# PSFB_power.net
KiCad netlist of a schematic drawn in Altium Designer
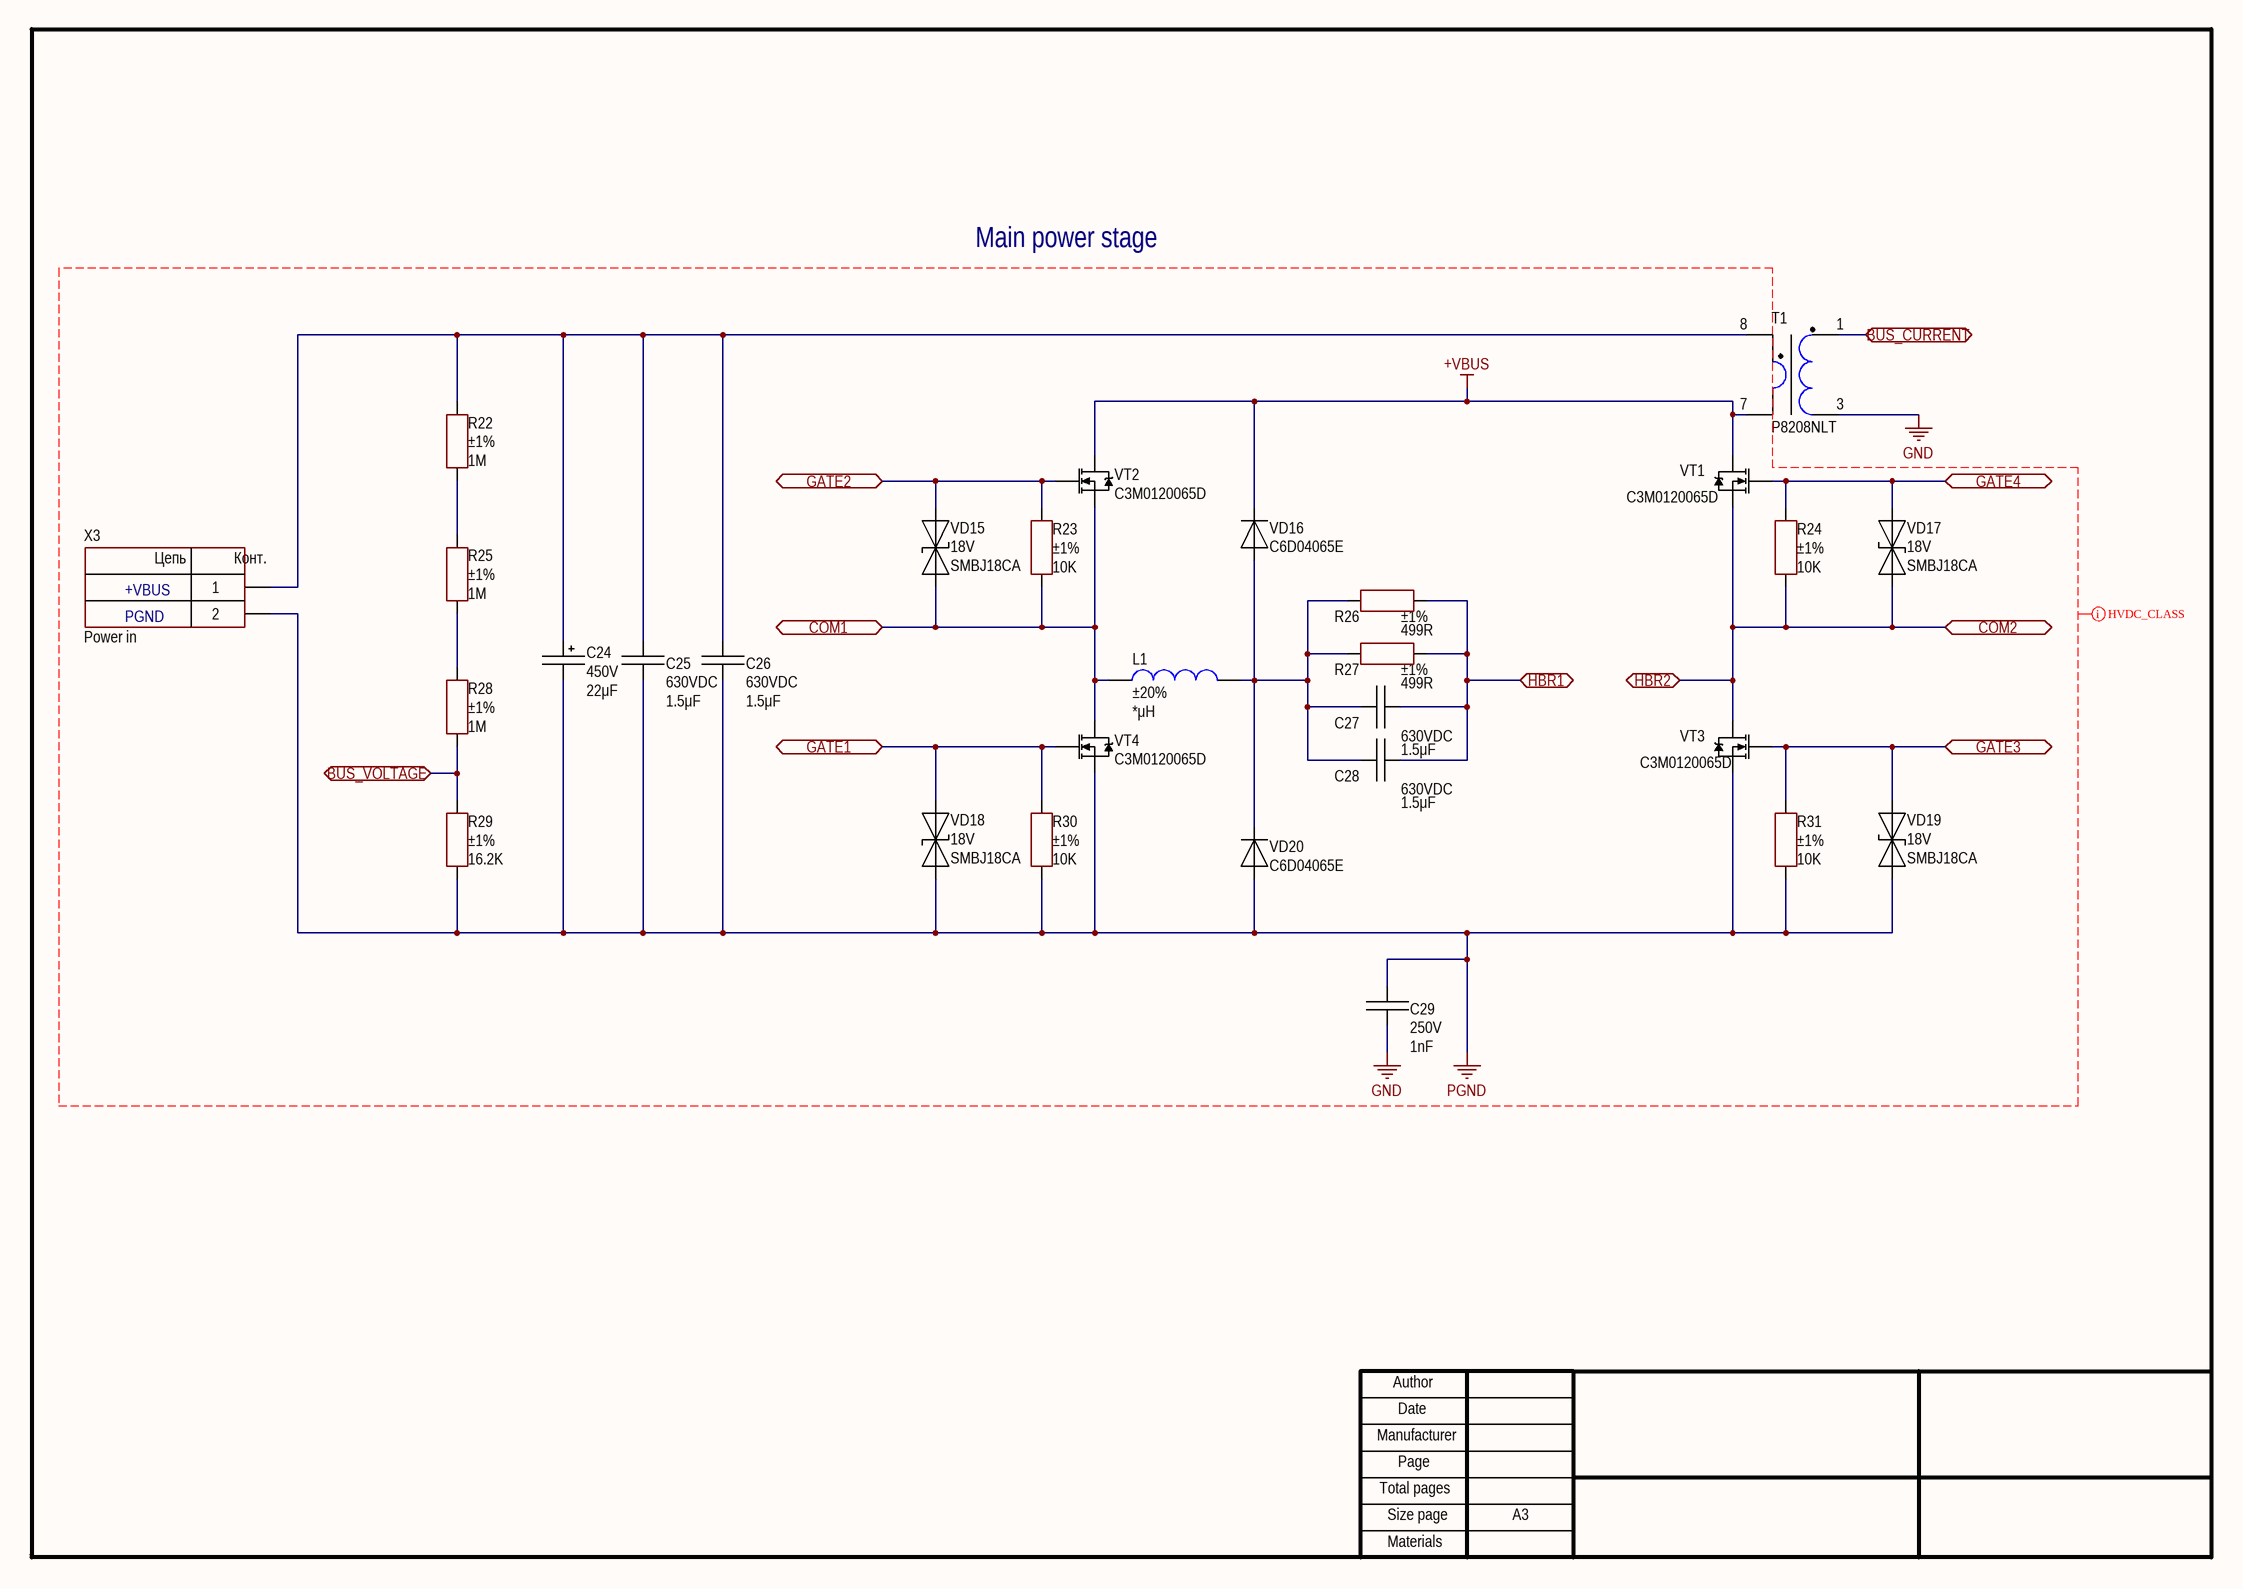
[diagram p0: PSFB_power.SchDoc]

(export (version "E")
  (design (tool "Eeschema 10.0.6"))
  (components
    (comp (ref "C24")
      (value "22μF")
      (footprint "CAP: D16C7.5H25")
      (description "22µF 450V Aluminum Electrolytic Capacitors Radial, Can  12000 Hrs @ 105°C")
      (fields
        (field (name "MANUFACTURER") "Rubycon")
        (field (name "PARTNUMBER") "A750KS337M1EAAE018")
        (field (name "VOLTAGE") "450V")
      )
      (libsource (lib "capacitor") (part "Aluminium"))
    )
    (comp (ref "C25")
      (value "1.5μF")
      (footprint "WCAP-FTBP_L31W16H25.5")
      (description "1.5µF Film Capacitor  630V Polypropylene (PP), Metallized RadialC")
      (fields
        (field (name "MANUFACTURER") "Würth Elektronik")
        (field (name "PARTNUMBER") "890303327008CS")
        (field (name "VOLTAGE") "630VDC")
      )
      (libsource (lib "capacitor") (part "Film"))
    )
    (comp (ref "C26")
      (value "1.5μF")
      (footprint "WCAP-FTBP_L31W16H25.5")
      (description "1.5µF Film Capacitor  630V Polypropylene (PP), Metallized RadialC")
      (fields
        (field (name "MANUFACTURER") "Würth Elektronik")
        (field (name "PARTNUMBER") "890303327008CS")
        (field (name "VOLTAGE") "630VDC")
      )
      (libsource (lib "capacitor") (part "Film"))
    )
    (comp (ref "C27")
      (value "1.5μF")
      (footprint "WCAP-FTBP_L31W16H25.5")
      (description "1.5µF Film Capacitor  630V Polypropylene (PP), Metallized RadialC")
      (fields
        (field (name "MANUFACTURER") "Würth Elektronik")
        (field (name "PARTNUMBER") "890303327008CS")
        (field (name "VOLTAGE") "630VDC")
      )
      (libsource (lib "capacitor") (part "Film"))
    )
    (comp (ref "C28")
      (value "1.5μF")
      (footprint "WCAP-FTBP_L31W16H25.5")
      (description "1.5µF Film Capacitor  630V Polypropylene (PP), Metallized RadialC")
      (fields
        (field (name "MANUFACTURER") "Würth Elektronik")
        (field (name "PARTNUMBER") "890303327008CS")
        (field (name "VOLTAGE") "630VDC")
      )
      (libsource (lib "capacitor") (part "Film"))
    )
    (comp (ref "C29")
      (value "1nF")
      (footprint "WCAP-CSSA_2211_H2.5")
      (description "1000pF ±10% 250V Ceramic Capacitor X7R 2211 (5728 Metric)")
      (fields
        (field (name "MANUFACTURER") "Yageo")
        (field (name "PARTNUMBER") "8853522130111")
        (field (name "VOLTAGE") "250V")
      )
      (libsource (lib "capacitor") (part "Ceramic_2211"))
    )
    (comp (ref "L1")
      (value "*μH")
      (footprint "IND: R26.9/14.7/11.2 (H)")
      (description "Custom inductor, DNP")
      (fields
        (field (name "MANUFACTURER") "Magnetics")
        (field (name "PARTNUMBER") "0077930A7")
        (field (name "TOLERANCE") "±20%")
      )
      (libsource (lib "inductor") (part "Inductor_R26.9/14.7/11.2"))
    )
    (comp (ref "R22")
      (value "1M")
      (footprint "RES: 1206")
      (description "1 MOhms ±1% 0.25W, 1/4W Chip Resistor 1206 (3216 Metric) Moisture Resistant Thick Film")
      (fields
        (field (name "MANUFACTURER") "Yageo")
        (field (name "PARTNUMBER") "RC1206FR-071ML")
        (field (name "TOLERANCE") "±1%")
      )
      (libsource (lib "resistor") (part "Resistor_1206"))
    )
    (comp (ref "R23")
      (value "10K")
      (footprint "RES: 0805")
      (description "10 kOhms ±1% 0.125W, 1/8W Chip Resistor 0805 (2012 Metric) Moisture Resistant Thick Film")
      (fields
        (field (name "MANUFACTURER") "Yageo")
        (field (name "PARTNUMBER") "RC0805FR-0710KL")
        (field (name "TOLERANCE") "±1%")
      )
      (libsource (lib "") (part "Resistor_0805_1"))
    )
    (comp (ref "R24")
      (value "10K")
      (footprint "RES: 0805")
      (description "10 kOhms ±1% 0.125W, 1/8W Chip Resistor 0805 (2012 Metric) Moisture Resistant Thick Film")
      (fields
        (field (name "MANUFACTURER") "Yageo")
        (field (name "PARTNUMBER") "RC0805FR-0710KL")
        (field (name "TOLERANCE") "±1%")
      )
      (libsource (lib "resistor") (part "Resistor_0805"))
    )
    (comp (ref "R25")
      (value "1M")
      (footprint "RES: 1206")
      (description "1 MOhms ±1% 0.25W, 1/4W Chip Resistor 1206 (3216 Metric) Moisture Resistant Thick Film")
      (fields
        (field (name "MANUFACTURER") "Yageo")
        (field (name "PARTNUMBER") "RC1206FR-071ML")
        (field (name "TOLERANCE") "±1%")
      )
      (libsource (lib "resistor") (part "Resistor_1206"))
    )
    (comp (ref "R26")
      (value "499R")
      (footprint "RES: 2512")
      (description "499 Ohms ±1% 1W Chip Resistor 2512 (6432 Metric) Moisture Resistant Thick Film")
      (fields
        (field (name "MANUFACTURER") "Yageo")
        (field (name "PARTNUMBER") "RC2512FK-07499RL")
        (field (name "TOLERANCE") "±1%")
      )
      (libsource (lib "resistor") (part "Resistor_2512"))
    )
    (comp (ref "R27")
      (value "499R")
      (footprint "RES: 2512")
      (description "499 Ohms ±1% 1W Chip Resistor 2512 (6432 Metric) Moisture Resistant Thick Film")
      (fields
        (field (name "MANUFACTURER") "Yageo")
        (field (name "PARTNUMBER") "RC2512FK-07499RL")
        (field (name "TOLERANCE") "±1%")
      )
      (libsource (lib "resistor") (part "Resistor_2512"))
    )
    (comp (ref "R28")
      (value "1M")
      (footprint "RES: 1206")
      (description "1 MOhms ±1% 0.25W, 1/4W Chip Resistor 1206 (3216 Metric) Moisture Resistant Thick Film")
      (fields
        (field (name "MANUFACTURER") "Yageo")
        (field (name "PARTNUMBER") "RC1206FR-071ML")
        (field (name "TOLERANCE") "±1%")
      )
      (libsource (lib "resistor") (part "Resistor_1206"))
    )
    (comp (ref "R29")
      (value "16.2K")
      (footprint "RES: 1206")
      (description "16.2 kOhms ±1% 0.25W, 1/4W Chip Resistor 1206 (3216 Metric) Moisture Resistant Thick Film")
      (fields
        (field (name "MANUFACTURER") "Yageo")
        (field (name "PARTNUMBER") "RC1206FR-0716K2L")
        (field (name "TOLERANCE") "±1%")
      )
      (libsource (lib "resistor") (part "Resistor_1206"))
    )
    (comp (ref "R30")
      (value "10K")
      (footprint "RES: 0805")
      (description "10 kOhms ±1% 0.125W, 1/8W Chip Resistor 0805 (2012 Metric) Moisture Resistant Thick Film")
      (fields
        (field (name "MANUFACTURER") "Yageo")
        (field (name "PARTNUMBER") "RC0805FR-0710KL")
        (field (name "TOLERANCE") "±1%")
      )
      (libsource (lib "") (part "Resistor_0805_1"))
    )
    (comp (ref "R31")
      (value "10K")
      (footprint "RES: 0805")
      (description "10 kOhms ±1% 0.125W, 1/8W Chip Resistor 0805 (2012 Metric) Moisture Resistant Thick Film")
      (fields
        (field (name "MANUFACTURER") "Yageo")
        (field (name "PARTNUMBER") "RC0805FR-0710KL")
        (field (name "TOLERANCE") "±1%")
      )
      (libsource (lib "resistor") (part "Resistor_0805"))
    )
    (comp (ref "T1")
      (value "~")
      (footprint "TRANS: P8208NLT")
      (description "1:100 Current Sense Transformer 50kHz ~ 1MHz 6mOhm Primary, 5.5Ohm Secondary 2mH Surface Mount")
      (fields
        (field (name "MANUFACTURER") "Pulse Electronics")
        (field (name "VALUEMANUFACTURERPARTNUMBER") "Current transformer, 1:100, 50...1000 kHz")
        (field (name "PARTNUMBER") "P8208NLT")
      )
      (libsource (lib "transformer") (part "Current_P8208NLT"))
    )
    (comp (ref "VD15")
      (value "~")
      (footprint "DIODE: SMB")
      (description "29.2V Clamp 20.6A Ipp Tvs Diode Surface Mount DO-214AA (SMBJ)")
      (fields
        (field (name "MANUFACTURER") "Diodes Incorporated")
        (field (name "VALUEMANUFACTURERPARTNUMBER") "TVS diode, 18V, 600W, , , SMB, -55...+150°C")
        (field (name "VOLTAGE") "18V")
        (field (name "PARTNUMBER") "SMBJ18CA")
      )
      (libsource (lib "diode") (part "TVS_single"))
    )
    (comp (ref "VD16")
      (value "~")
      (footprint "DPAK (D)")
      (description "Diode Silicon Carbide Schottky 650V 8A (DC) Surface Mount TO-252-2")
      (fields
        (field (name "MANUFACTURER") "Wolfspeed")
        (field (name "VALUEMANUFACTURERPARTNUMBER") "Single diode, 650V, 1A, 1.5V, 0ns, TO-252-2, -55...+150°C")
        (field (name "PARTNUMBER") "C6D04065E")
      )
      (libsource (lib "diode") (part "Diode_single"))
    )
    (comp (ref "VD17")
      (value "~")
      (footprint "DIODE: SMB")
      (description "29.2V Clamp 20.6A Ipp Tvs Diode Surface Mount DO-214AA (SMBJ)")
      (fields
        (field (name "MANUFACTURER") "Diodes Incorporated")
        (field (name "VALUEMANUFACTURERPARTNUMBER") "TVS diode, 18V, 600W, , , SMB, -55...+150°C")
        (field (name "VOLTAGE") "18V")
        (field (name "PARTNUMBER") "SMBJ18CA")
      )
      (libsource (lib "diode") (part "TVS_single"))
    )
    (comp (ref "VD18")
      (value "~")
      (footprint "DIODE: SMB")
      (description "29.2V Clamp 20.6A Ipp Tvs Diode Surface Mount DO-214AA (SMBJ)")
      (fields
        (field (name "MANUFACTURER") "Diodes Incorporated")
        (field (name "VALUEMANUFACTURERPARTNUMBER") "TVS diode, 18V, 600W, , , SMB, -55...+150°C")
        (field (name "VOLTAGE") "18V")
        (field (name "PARTNUMBER") "SMBJ18CA")
      )
      (libsource (lib "diode") (part "TVS_single"))
    )
    (comp (ref "VD19")
      (value "~")
      (footprint "DIODE: SMB")
      (description "29.2V Clamp 20.6A Ipp Tvs Diode Surface Mount DO-214AA (SMBJ)")
      (fields
        (field (name "MANUFACTURER") "Diodes Incorporated")
        (field (name "VALUEMANUFACTURERPARTNUMBER") "TVS diode, 18V, 600W, , , SMB, -55...+150°C")
        (field (name "VOLTAGE") "18V")
        (field (name "PARTNUMBER") "SMBJ18CA")
      )
      (libsource (lib "diode") (part "TVS_single"))
    )
    (comp (ref "VD20")
      (value "~")
      (footprint "DPAK (D)")
      (description "Diode Silicon Carbide Schottky 650V 8A (DC) Surface Mount TO-252-2")
      (fields
        (field (name "MANUFACTURER") "Wolfspeed")
        (field (name "VALUEMANUFACTURERPARTNUMBER") "Single diode, 650V, 1A, 1.5V, 0ns, TO-252-2, -55...+150°C")
        (field (name "PARTNUMBER") "C6D04065E")
      )
      (libsource (lib "diode") (part "Diode_single"))
    )
    (comp (ref "VT1")
      (value "~")
      (footprint "TO247(H)")
      (description "N-Channel 650V 22A (Tc) 98W (Tc) SiC MOSFET Through Hole TO-247-3")
      (fields
        (field (name "MANUFACTURER") "Infineon Technologies")
        (field (name "VALUEMANUFACTURERPARTNUMBER") "MOSFET N-channel transistor, 650V, 22A, 26nC, 98W, 120mOhm, 756pF, TO247-3, -55...+150°C")
        (field (name "PARTNUMBER") "C3M0120065D")
      )
      (libsource (lib "transistor") (part "MOSFET_N_123"))
    )
    (comp (ref "VT2")
      (value "~")
      (footprint "TO247(H)")
      (description "N-Channel 650V 22A (Tc) 98W (Tc) SiC MOSFET Through Hole TO-247-3")
      (fields
        (field (name "MANUFACTURER") "Infineon Technologies")
        (field (name "VALUEMANUFACTURERPARTNUMBER") "MOSFET N-channel transistor, 650V, 22A, 26nC, 98W, 120mOhm, 756pF, TO247-3, -55...+150°C")
        (field (name "PARTNUMBER") "C3M0120065D")
      )
      (libsource (lib "transistor") (part "MOSFET_N_123"))
    )
    (comp (ref "VT3")
      (value "~")
      (footprint "TO247(H)")
      (description "N-Channel 650V 22A (Tc) 98W (Tc) SiC MOSFET Through Hole TO-247-3")
      (fields
        (field (name "MANUFACTURER") "Infineon Technologies")
        (field (name "VALUEMANUFACTURERPARTNUMBER") "MOSFET N-channel transistor, 650V, 22A, 26nC, 98W, 120mOhm, 756pF, TO247-3, -55...+150°C")
        (field (name "PARTNUMBER") "C3M0120065D")
      )
      (libsource (lib "transistor") (part "MOSFET_N_123"))
    )
    (comp (ref "VT4")
      (value "~")
      (footprint "TO247(H)")
      (description "N-Channel 650V 22A (Tc) 98W (Tc) SiC MOSFET Through Hole TO-247-3")
      (fields
        (field (name "MANUFACTURER") "Infineon Technologies")
        (field (name "VALUEMANUFACTURERPARTNUMBER") "MOSFET N-channel transistor, 650V, 22A, 26nC, 98W, 120mOhm, 756pF, TO247-3, -55...+150°C")
        (field (name "PARTNUMBER") "C3M0120065D")
      )
      (libsource (lib "transistor") (part "MOSFET_N_123"))
    )
    (comp (ref "X3")
      (value "~")
      (footprint "CON: 2453690000")
      (description "2 Position Wire to Board Terminal Block Horizontal with Board 0.394\" (10.00mm) Through Hole")
      (fields
        (field (name "MANUFACTURER") "Weidmüller")
        (field (name "VALUEMANUFACTURERPARTNUMBER") "Connector, 2pin, 10mm, 600V, 60A")
        (field (name "COMMENTTEXT") "Power in")
      )
      (libsource (lib "connector") (part "LUF-10.00"))
    )
  )
  (nets
    (net (code "1") (name "+VBUS") (class "Default")
      (node (ref "T1") (pin "7") (pinfunction "7_7") (pintype "power_in"))
      (node (ref "VD16") (pin "2") (pinfunction "2_2") (pintype "passive"))
      (node (ref "VT1") (pin "2") (pinfunction "D_2") (pintype "passive"))
      (node (ref "VT2") (pin "2") (pinfunction "D_2") (pintype "passive"))
    )
    (net (code "2") (name "/BUS_CURRENT") (class "Default")
      (node (ref "T1") (pin "1") (pinfunction "1_1") (pintype "power_in"))
    )
    (net (code "3") (name "/BUS_VOLTAGE") (class "Default")
      (node (ref "R28") (pin "1") (pinfunction "1_1") (pintype "passive"))
      (node (ref "R29") (pin "2") (pinfunction "2_2") (pintype "passive"))
    )
    (net (code "4") (name "/COM1") (class "Default")
      (node (ref "L1") (pin "2") (pinfunction "2_2") (pintype "passive"))
      (node (ref "R23") (pin "1") (pinfunction "1_1") (pintype "passive"))
      (node (ref "VD15") (pin "2") (pinfunction "C_2") (pintype "passive"))
      (node (ref "VT2") (pin "3") (pinfunction "S_3") (pintype "passive"))
      (node (ref "VT4") (pin "2") (pinfunction "D_2") (pintype "passive"))
    )
    (net (code "5") (name "/COM2") (class "Default")
      (node (ref "R24") (pin "1") (pinfunction "1_1") (pintype "passive"))
      (node (ref "VD17") (pin "2") (pinfunction "C_2") (pintype "passive"))
      (node (ref "VT1") (pin "3") (pinfunction "S_3") (pintype "passive"))
      (node (ref "VT3") (pin "2") (pinfunction "D_2") (pintype "passive"))
    )
    (net (code "6") (name "/GATE1") (class "Default")
      (node (ref "R30") (pin "2") (pinfunction "2_2") (pintype "passive"))
      (node (ref "VD18") (pin "1") (pinfunction "A_1") (pintype "passive"))
      (node (ref "VT4") (pin "1") (pinfunction "G_1") (pintype "passive"))
    )
    (net (code "7") (name "/GATE2") (class "Default")
      (node (ref "R23") (pin "2") (pinfunction "2_2") (pintype "passive"))
      (node (ref "VD15") (pin "1") (pinfunction "A_1") (pintype "passive"))
      (node (ref "VT2") (pin "1") (pinfunction "G_1") (pintype "passive"))
    )
    (net (code "8") (name "/GATE3") (class "Default")
      (node (ref "R31") (pin "2") (pinfunction "2_2") (pintype "passive"))
      (node (ref "VD19") (pin "1") (pinfunction "A_1") (pintype "passive"))
      (node (ref "VT3") (pin "1") (pinfunction "G_1") (pintype "passive"))
    )
    (net (code "9") (name "/GATE4") (class "Default")
      (node (ref "R24") (pin "2") (pinfunction "2_2") (pintype "passive"))
      (node (ref "VD17") (pin "1") (pinfunction "A_1") (pintype "passive"))
      (node (ref "VT1") (pin "1") (pinfunction "G_1") (pintype "passive"))
    )
    (net (code "10") (name "/HBR1") (class "Default")
      (node (ref "C27") (pin "2") (pinfunction "2_2") (pintype "passive"))
      (node (ref "C28") (pin "2") (pinfunction "2_2") (pintype "passive"))
      (node (ref "R26") (pin "2") (pinfunction "2_2") (pintype "passive"))
      (node (ref "R27") (pin "2") (pinfunction "2_2") (pintype "passive"))
    )
    (net (code "11") (name "GND") (class "Default")
      (node (ref "C29") (pin "2") (pinfunction "2_2") (pintype "passive"))
      (node (ref "T1") (pin "3") (pinfunction "3_3") (pintype "power_in"))
    )
    (net (code "12") (name "Net-(C24-Pad1)") (class "Default")
      (node (ref "C24") (pin "1") (pinfunction "1_1") (pintype "passive"))
      (node (ref "C25") (pin "2") (pinfunction "2_2") (pintype "passive"))
      (node (ref "C26") (pin "2") (pinfunction "2_2") (pintype "passive"))
      (node (ref "R22") (pin "2") (pinfunction "2_2") (pintype "passive"))
      (node (ref "T1") (pin "8") (pinfunction "8_8") (pintype "power_in"))
      (node (ref "X3") (pin "1") (pinfunction "1_1") (pintype "passive"))
    )
    (net (code "13") (name "Net-(C27-Pad1)") (class "Default")
      (node (ref "C27") (pin "1") (pinfunction "1_1") (pintype "passive"))
      (node (ref "C28") (pin "1") (pinfunction "1_1") (pintype "passive"))
      (node (ref "L1") (pin "1") (pinfunction "1_1") (pintype "passive"))
      (node (ref "R26") (pin "1") (pinfunction "1_1") (pintype "passive"))
      (node (ref "R27") (pin "1") (pinfunction "1_1") (pintype "passive"))
      (node (ref "VD16") (pin "1") (pinfunction "1_1") (pintype "passive"))
      (node (ref "VD20") (pin "2") (pinfunction "2_2") (pintype "passive"))
    )
    (net (code "14") (name "Net-(R22-Pad1)") (class "Default")
      (node (ref "R22") (pin "1") (pinfunction "1_1") (pintype "passive"))
      (node (ref "R25") (pin "2") (pinfunction "2_2") (pintype "passive"))
    )
    (net (code "15") (name "Net-(R25-Pad1)") (class "Default")
      (node (ref "R25") (pin "1") (pinfunction "1_1") (pintype "passive"))
      (node (ref "R28") (pin "2") (pinfunction "2_2") (pintype "passive"))
    )
    (net (code "16") (name "PGND") (class "Default")
      (node (ref "C24") (pin "2") (pinfunction "2_2") (pintype "passive"))
      (node (ref "C25") (pin "1") (pinfunction "1_1") (pintype "passive"))
      (node (ref "C26") (pin "1") (pinfunction "1_1") (pintype "passive"))
      (node (ref "C29") (pin "1") (pinfunction "1_1") (pintype "passive"))
      (node (ref "R29") (pin "1") (pinfunction "1_1") (pintype "passive"))
      (node (ref "R30") (pin "1") (pinfunction "1_1") (pintype "passive"))
      (node (ref "R31") (pin "1") (pinfunction "1_1") (pintype "passive"))
      (node (ref "VD18") (pin "2") (pinfunction "C_2") (pintype "passive"))
      (node (ref "VD19") (pin "2") (pinfunction "C_2") (pintype "passive"))
      (node (ref "VD20") (pin "1") (pinfunction "1_1") (pintype "passive"))
      (node (ref "VT3") (pin "3") (pinfunction "S_3") (pintype "passive"))
      (node (ref "VT4") (pin "3") (pinfunction "S_3") (pintype "passive"))
      (node (ref "X3") (pin "2") (pinfunction "2_2") (pintype "passive"))
    )
  )
)
